# Project_Espro.net
KiCad netlist of a schematic drawn in EasyEDA
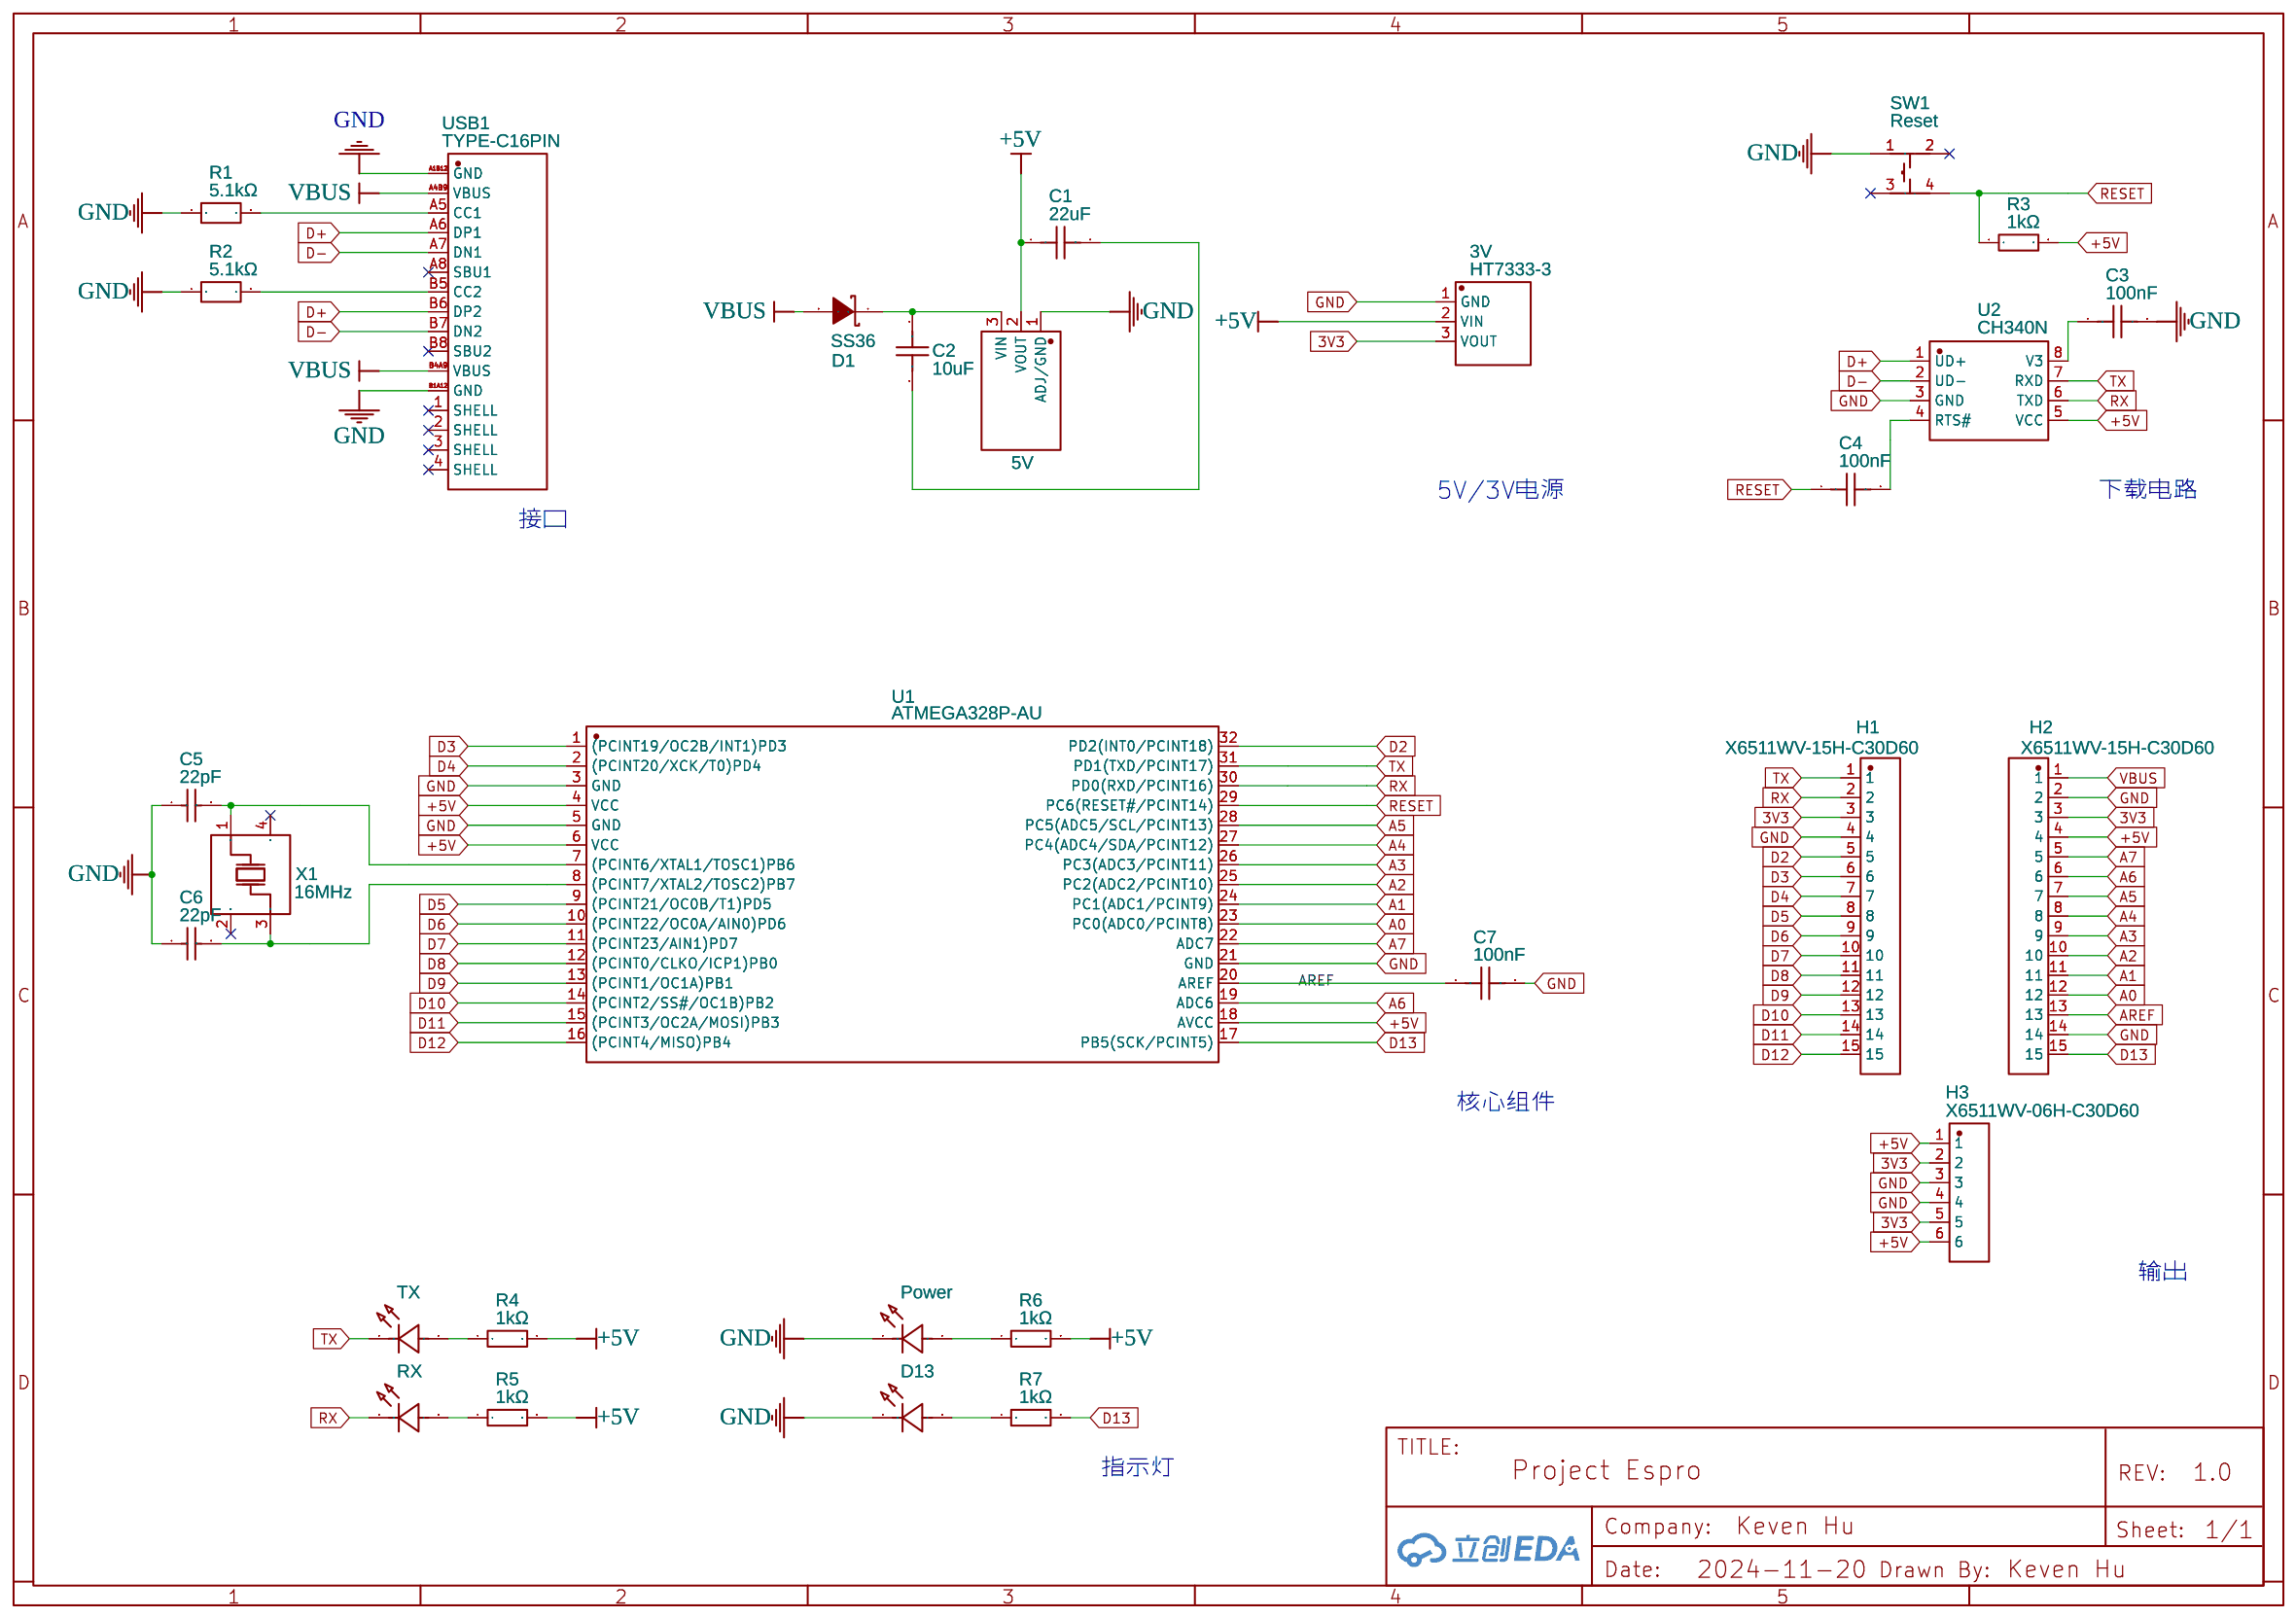
[diagram p0: schematic sheet]

(export (version "E")
  (design (tool "Eeschema 10.0.6"))
  (components
    (comp (ref "3V")
      (value "HT7333-3")
      (fields (field (name "Manufacturer") "HOLTEK"))
      (libsource (lib "") (part "HT7333-3"))
    )
    (comp (ref "5V")
      (value "5V")
      (fields (field (name "Manufacturer Part") "AMS1117-5.0") (field (name "Manufacturer") "Slkor(萨科微)"))
      (libsource (lib "") (part "AMS1117-5.0_C880753"))
    )
    (comp (ref "C1")
      (value "22uF")
      (fields
        (field (name "Manufacturer Part") "HGC0603R5226M100NTHJ")
        (field (name "Manufacturer") "Chinocera(华瓷)")
      )
      (libsource (lib "") (part "HGC0603R5226M100NTHJ"))
    )
    (comp (ref "C2")
      (value "10uF")
      (fields
        (field (name "Manufacturer Part") "CGA0603X5R106K100JT")
        (field (name "Manufacturer") "HRE(芯声)")
      )
      (libsource (lib "") (part "CGA0603X5R106K100JT"))
    )
    (comp (ref "C3")
      (value "100nF")
      (fields
        (field (name "Manufacturer Part") "CGA0603X7R104K500JT")
        (field (name "Manufacturer") "HRE(芯声)")
      )
      (libsource (lib "") (part "CGA0603X7R104K500JT"))
    )
    (comp (ref "C4")
      (value "100nF")
      (fields
        (field (name "Manufacturer Part") "CGA0603X7R104K500JT")
        (field (name "Manufacturer") "HRE(芯声)")
      )
      (libsource (lib "") (part "CGA0603X7R104K500JT"))
    )
    (comp (ref "C5")
      (value "22pF")
      (fields
        (field (name "Manufacturer Part") "CC0603JRNPO9BN220")
        (field (name "Manufacturer") "YAGEO(国巨)")
      )
      (libsource (lib "") (part "CC0603JRNPO9BN220"))
    )
    (comp (ref "C6")
      (value "22pF")
      (fields
        (field (name "Manufacturer Part") "CC0603JRNPO9BN220")
        (field (name "Manufacturer") "YAGEO(国巨)")
      )
      (libsource (lib "") (part "CC0603JRNPO9BN220"))
    )
    (comp (ref "C7")
      (value "100nF")
      (fields
        (field (name "Manufacturer Part") "CGA0603X7R104K500JT")
        (field (name "Manufacturer") "HRE(芯声)")
      )
      (libsource (lib "") (part "CGA0603X7R104K500JT"))
    )
    (comp (ref "D1")
      (value "SS36")
      (fields (field (name "Manufacturer") "MDD"))
      (libsource (lib "") (part "SS36"))
    )
    (comp (ref "H1")
      (value "X6511WV-15H-C30D60")
      (fields (field (name "Manufacturer") "XKB Connectivity"))
      (libsource (lib "") (part "X6511WV-15H-C30D60"))
    )
    (comp (ref "H2")
      (value "X6511WV-15H-C30D60")
      (fields (field (name "Manufacturer") "XKB Connectivity"))
      (libsource (lib "") (part "X6511WV-15H-C30D60_1"))
    )
    (comp (ref "H3")
      (value "X6511WV-06H-C30D60")
      (fields (field (name "Manufacturer") "XKB Connectivity"))
      (libsource (lib "") (part "X6511WV-06H-C30D60"))
    )
    (comp (ref "LED1")
      (value "TX")
      (fields
        (field (name "Manufacturer Part") "XL-1608UWC-06A")
        (field (name "Manufacturer") "XINGLIGHT(成兴光)")
      )
      (libsource (lib "") (part "XL-1608UWC-06A"))
    )
    (comp (ref "LED2")
      (value "RX")
      (fields
        (field (name "Manufacturer Part") "XL-1608UWC-06A")
        (field (name "Manufacturer") "XINGLIGHT(成兴光)")
      )
      (libsource (lib "") (part "XL-1608UWC-06A"))
    )
    (comp (ref "LED3")
      (value "Power")
      (fields
        (field (name "Manufacturer Part") "XL-1608UWC-06A")
        (field (name "Manufacturer") "XINGLIGHT(成兴光)")
      )
      (libsource (lib "") (part "XL-1608UWC-06A"))
    )
    (comp (ref "LED4")
      (value "D13")
      (fields
        (field (name "Manufacturer Part") "XL-1608UWC-06A")
        (field (name "Manufacturer") "XINGLIGHT(成兴光)")
      )
      (libsource (lib "") (part "XL-1608UWC-06A"))
    )
    (comp (ref "R1")
      (value "5.1kΩ")
      (fields (field (name "Manufacturer Part") "FRC0603F5101TS") (field (name "Manufacturer") "FOJAN(富捷)"))
      (libsource (lib "") (part "FRC0603F5101TS"))
    )
    (comp (ref "R2")
      (value "5.1kΩ")
      (fields (field (name "Manufacturer Part") "FRC0603F5101TS") (field (name "Manufacturer") "FOJAN(富捷)"))
      (libsource (lib "") (part "FRC0603F5101TS"))
    )
    (comp (ref "R3")
      (value "1kΩ")
      (fields (field (name "Manufacturer Part") "RC0603FR-071KL") (field (name "Manufacturer") "YAGEO(国巨)"))
      (libsource (lib "") (part "RC0603FR-071KL"))
    )
    (comp (ref "R4")
      (value "1kΩ")
      (fields (field (name "Manufacturer Part") "RC0603FR-071KL") (field (name "Manufacturer") "YAGEO(国巨)"))
      (libsource (lib "") (part "RC0603FR-071KL"))
    )
    (comp (ref "R5")
      (value "1kΩ")
      (fields (field (name "Manufacturer Part") "RC0603FR-071KL") (field (name "Manufacturer") "YAGEO(国巨)"))
      (libsource (lib "") (part "RC0603FR-071KL"))
    )
    (comp (ref "R6")
      (value "1kΩ")
      (fields (field (name "Manufacturer Part") "RC0603FR-071KL") (field (name "Manufacturer") "YAGEO(国巨)"))
      (libsource (lib "") (part "RC0603FR-071KL"))
    )
    (comp (ref "R7")
      (value "1kΩ")
      (fields (field (name "Manufacturer Part") "RC0603FR-071KL") (field (name "Manufacturer") "YAGEO(国巨)"))
      (libsource (lib "") (part "RC0603FR-071KL"))
    )
    (comp (ref "SW1")
      (value "Reset")
      (fields (field (name "Manufacturer Part") "TS3425BA") (field (name "Manufacturer") "SHOU HAN(首韩)"))
      (libsource (lib "") (part "TS3425BA"))
    )
    (comp (ref "U1")
      (value "ATMEGA328P-AU")
      (fields (field (name "Manufacturer") "MICROCHIP"))
      (libsource (lib "") (part "ATMEGA328P-AU"))
    )
    (comp (ref "U2")
      (value "CH340N")
      (fields (field (name "Manufacturer") "WCH(Jiangsu Qin Heng)"))
      (libsource (lib "") (part "CH340N"))
    )
    (comp (ref "USB1")
      (value "TYPE-C16PIN")
      (fields (field (name "Manufacturer") "SHOU HAN"))
      (libsource (lib "") (part "TYPE-C16PIN"))
    )
    (comp (ref "X1")
      (value "16MHz")
      (fields (field (name "Manufacturer Part") "X322516MLB4SI") (field (name "Manufacturer") "YXC"))
      (libsource (lib "") (part "X322516MLB4SI"))
    )
  )
  (nets
    (net (code "1") (name "+5V") (class "Default")
      (node (ref "3V") (pin "2") (pinfunction "VIN_2") (pintype "unspecified"))
      (node (ref "5V") (pin "2") (pinfunction "VOUT_2") (pintype "unspecified"))
      (node (ref "C1") (pin "1") (pinfunction "1_1") (pintype "unspecified"))
      (node (ref "H2") (pin "4") (pinfunction "4_4") (pintype "unspecified"))
      (node (ref "H3") (pin "1") (pinfunction "1_1") (pintype "unspecified"))
      (node (ref "H3") (pin "6") (pinfunction "6_6") (pintype "unspecified"))
      (node (ref "R3") (pin "2") (pinfunction "2_2") (pintype "input"))
      (node (ref "R4") (pin "2") (pinfunction "2_2") (pintype "input"))
      (node (ref "R5") (pin "2") (pinfunction "2_2") (pintype "input"))
      (node (ref "R6") (pin "2") (pinfunction "2_2") (pintype "input"))
      (node (ref "U1") (pin "18") (pinfunction "AVCC_18") (pintype "unspecified"))
      (node (ref "U1") (pin "4") (pinfunction "VCC_4") (pintype "unspecified"))
      (node (ref "U1") (pin "6") (pinfunction "VCC_6") (pintype "unspecified"))
      (node (ref "U2") (pin "5") (pinfunction "VCC_5") (pintype "unspecified"))
    )
    (net (code "2") (name "3V3") (class "Default")
      (node (ref "3V") (pin "3") (pinfunction "VOUT_3") (pintype "unspecified"))
      (node (ref "H1") (pin "3") (pinfunction "3_3") (pintype "unspecified"))
      (node (ref "H2") (pin "3") (pinfunction "3_3") (pintype "unspecified"))
      (node (ref "H3") (pin "2") (pinfunction "2_2") (pintype "unspecified"))
      (node (ref "H3") (pin "5") (pinfunction "5_5") (pintype "unspecified"))
    )
    (net (code "3") (name "A0") (class "Default")
      (node (ref "H2") (pin "12") (pinfunction "12_12") (pintype "unspecified"))
      (node (ref "U1") (pin "23") (pinfunction "PC0(ADC0/PCINT8)_23") (pintype "unspecified"))
    )
    (net (code "4") (name "A1") (class "Default")
      (node (ref "H2") (pin "11") (pinfunction "11_11") (pintype "unspecified"))
      (node (ref "U1") (pin "24") (pinfunction "PC1(ADC1/PCINT9)_24") (pintype "unspecified"))
    )
    (net (code "5") (name "A2") (class "Default")
      (node (ref "H2") (pin "10") (pinfunction "10_10") (pintype "unspecified"))
      (node (ref "U1") (pin "25") (pinfunction "PC2(ADC2/PCINT10)_25") (pintype "unspecified"))
    )
    (net (code "6") (name "A3") (class "Default")
      (node (ref "H2") (pin "9") (pinfunction "9_9") (pintype "unspecified"))
      (node (ref "U1") (pin "26") (pinfunction "PC3(ADC3/PCINT11)_26") (pintype "unspecified"))
    )
    (net (code "7") (name "A4") (class "Default")
      (node (ref "H2") (pin "8") (pinfunction "8_8") (pintype "unspecified"))
      (node (ref "U1") (pin "27") (pinfunction "PC4(ADC4/SDA/PCINT12)_27") (pintype "unspecified"))
    )
    (net (code "8") (name "A5") (class "Default")
      (node (ref "H2") (pin "7") (pinfunction "7_7") (pintype "unspecified"))
      (node (ref "U1") (pin "28") (pinfunction "PC5(ADC5/SCL/PCINT13)_28") (pintype "unspecified"))
    )
    (net (code "9") (name "A6") (class "Default")
      (node (ref "H2") (pin "6") (pinfunction "6_6") (pintype "unspecified"))
      (node (ref "U1") (pin "19") (pinfunction "ADC6_19") (pintype "unspecified"))
    )
    (net (code "10") (name "A7") (class "Default")
      (node (ref "H2") (pin "5") (pinfunction "5_5") (pintype "unspecified"))
      (node (ref "U1") (pin "22") (pinfunction "ADC7_22") (pintype "unspecified"))
    )
    (net (code "11") (name "AREF") (class "Default")
      (node (ref "C7") (pin "1") (pinfunction "1_1") (pintype "unspecified"))
      (node (ref "H2") (pin "13") (pinfunction "13_13") (pintype "unspecified"))
      (node (ref "U1") (pin "20") (pinfunction "AREF_20") (pintype "unspecified"))
    )
    (net (code "12") (name "D+") (class "Default")
      (node (ref "U2") (pin "1") (pinfunction "UD+_1") (pintype "unspecified"))
      (node (ref "USB1") (pin "A6") (pinfunction "DP1_A6") (pintype "unspecified"))
      (node (ref "USB1") (pin "B6") (pinfunction "DP2_B6") (pintype "unspecified"))
    )
    (net (code "13") (name "D-") (class "Default")
      (node (ref "U2") (pin "2") (pinfunction "UD-_2") (pintype "unspecified"))
      (node (ref "USB1") (pin "A7") (pinfunction "DN1_A7") (pintype "unspecified"))
      (node (ref "USB1") (pin "B7") (pinfunction "DN2_B7") (pintype "unspecified"))
    )
    (net (code "14") (name "D2") (class "Default")
      (node (ref "H1") (pin "5") (pinfunction "5_5") (pintype "unspecified"))
      (node (ref "U1") (pin "32") (pinfunction "PD2(INT0/PCINT18)_32") (pintype "unspecified"))
    )
    (net (code "15") (name "D3") (class "Default")
      (node (ref "H1") (pin "6") (pinfunction "6_6") (pintype "unspecified"))
      (node (ref "U1") (pin "1") (pinfunction "(PCINT19/OC2B/INT1)PD3_1") (pintype "unspecified"))
    )
    (net (code "16") (name "D4") (class "Default")
      (node (ref "H1") (pin "7") (pinfunction "7_7") (pintype "unspecified"))
      (node (ref "U1") (pin "2") (pinfunction "(PCINT20/XCK/T0)PD4_2") (pintype "unspecified"))
    )
    (net (code "17") (name "D5") (class "Default")
      (node (ref "H1") (pin "8") (pinfunction "8_8") (pintype "unspecified"))
      (node (ref "U1") (pin "9") (pinfunction "(PCINT21/OC0B/T1)PD5_9") (pintype "unspecified"))
    )
    (net (code "18") (name "D6") (class "Default")
      (node (ref "H1") (pin "9") (pinfunction "9_9") (pintype "unspecified"))
      (node (ref "U1") (pin "10") (pinfunction "(PCINT22/OC0A/AIN0)PD6_10") (pintype "unspecified"))
    )
    (net (code "19") (name "D7") (class "Default")
      (node (ref "H1") (pin "10") (pinfunction "10_10") (pintype "unspecified"))
      (node (ref "U1") (pin "11") (pinfunction "(PCINT23/AIN1)PD7_11") (pintype "unspecified"))
    )
    (net (code "20") (name "D8") (class "Default")
      (node (ref "H1") (pin "11") (pinfunction "11_11") (pintype "unspecified"))
      (node (ref "U1") (pin "12") (pinfunction "(PCINT0/CLKO/ICP1)PB0_12") (pintype "unspecified"))
    )
    (net (code "21") (name "D9") (class "Default")
      (node (ref "H1") (pin "12") (pinfunction "12_12") (pintype "unspecified"))
      (node (ref "U1") (pin "13") (pinfunction "(PCINT1/OC1A)PB1_13") (pintype "unspecified"))
    )
    (net (code "22") (name "D10") (class "Default")
      (node (ref "H1") (pin "13") (pinfunction "13_13") (pintype "unspecified"))
      (node (ref "U1") (pin "14") (pinfunction "(PCINT2/SS#/OC1B)PB2_14") (pintype "unspecified"))
    )
    (net (code "23") (name "D11") (class "Default")
      (node (ref "H1") (pin "14") (pinfunction "14_14") (pintype "unspecified"))
      (node (ref "U1") (pin "15") (pinfunction "(PCINT3/OC2A/MOSI)PB3_15") (pintype "unspecified"))
    )
    (net (code "24") (name "D12") (class "Default")
      (node (ref "H1") (pin "15") (pinfunction "15_15") (pintype "unspecified"))
      (node (ref "U1") (pin "16") (pinfunction "(PCINT4/MISO)PB4_16") (pintype "unspecified"))
    )
    (net (code "25") (name "D13") (class "Default")
      (node (ref "H2") (pin "15") (pinfunction "15_15") (pintype "unspecified"))
      (node (ref "R7") (pin "2") (pinfunction "2_2") (pintype "input"))
      (node (ref "U1") (pin "17") (pinfunction "PB5(SCK/PCINT5)_17") (pintype "unspecified"))
    )
    (net (code "26") (name "GND") (class "Default")
      (node (ref "3V") (pin "1") (pinfunction "GND_1") (pintype "unspecified"))
      (node (ref "5V") (pin "1") (pinfunction "ADJ/GND_1") (pintype "unspecified"))
      (node (ref "C3") (pin "2") (pinfunction "2_2") (pintype "unspecified"))
      (node (ref "C5") (pin "1") (pinfunction "1_1") (pintype "input"))
      (node (ref "C6") (pin "1") (pinfunction "1_1") (pintype "input"))
      (node (ref "C7") (pin "2") (pinfunction "2_2") (pintype "unspecified"))
      (node (ref "H1") (pin "4") (pinfunction "4_4") (pintype "unspecified"))
      (node (ref "H2") (pin "14") (pinfunction "14_14") (pintype "unspecified"))
      (node (ref "H2") (pin "2") (pinfunction "2_2") (pintype "unspecified"))
      (node (ref "H3") (pin "3") (pinfunction "3_3") (pintype "unspecified"))
      (node (ref "H3") (pin "4") (pinfunction "4_4") (pintype "unspecified"))
      (node (ref "LED3") (pin "1") (pinfunction "K_1") (pintype "unspecified"))
      (node (ref "LED4") (pin "1") (pinfunction "K_1") (pintype "unspecified"))
      (node (ref "R1") (pin "1") (pinfunction "1_1") (pintype "unspecified"))
      (node (ref "R2") (pin "1") (pinfunction "1_1") (pintype "unspecified"))
      (node (ref "SW1") (pin "1") (pinfunction "1_1") (pintype "unspecified"))
      (node (ref "U1") (pin "21") (pinfunction "GND_21") (pintype "unspecified"))
      (node (ref "U1") (pin "3") (pinfunction "GND_3") (pintype "unspecified"))
      (node (ref "U1") (pin "5") (pinfunction "GND_5") (pintype "unspecified"))
      (node (ref "U2") (pin "3") (pinfunction "GND_3") (pintype "unspecified"))
      (node (ref "USB1") (pin "A1B12") (pinfunction "GND_A1B12") (pintype "unspecified"))
      (node (ref "USB1") (pin "B1A12") (pinfunction "GND_B1A12") (pintype "unspecified"))
    )
    (net (code "27") (name "Net-(5V-VIN)") (class "Default")
      (node (ref "5V") (pin "3") (pinfunction "VIN_3") (pintype "unspecified"))
      (node (ref "C2") (pin "1") (pinfunction "1_1") (pintype "unspecified"))
      (node (ref "D1") (pin "1") (pinfunction "K_1") (pintype "unspecified"))
    )
    (net (code "28") (name "Net-(C1-Pad2)") (class "Default")
      (node (ref "C1") (pin "2") (pinfunction "2_2") (pintype "unspecified"))
      (node (ref "C2") (pin "2") (pinfunction "2_2") (pintype "unspecified"))
    )
    (net (code "29") (name "Net-(LED1-A)") (class "Default")
      (node (ref "LED1") (pin "2") (pinfunction "A_2") (pintype "unspecified"))
      (node (ref "R4") (pin "1") (pinfunction "1_1") (pintype "input"))
    )
    (net (code "30") (name "Net-(LED2-A)") (class "Default")
      (node (ref "LED2") (pin "2") (pinfunction "A_2") (pintype "unspecified"))
      (node (ref "R5") (pin "1") (pinfunction "1_1") (pintype "input"))
    )
    (net (code "31") (name "Net-(LED3-A)") (class "Default")
      (node (ref "LED3") (pin "2") (pinfunction "A_2") (pintype "unspecified"))
      (node (ref "R6") (pin "1") (pinfunction "1_1") (pintype "input"))
    )
    (net (code "32") (name "Net-(LED4-A)") (class "Default")
      (node (ref "LED4") (pin "2") (pinfunction "A_2") (pintype "unspecified"))
      (node (ref "R7") (pin "1") (pinfunction "1_1") (pintype "input"))
    )
    (net (code "33") (name "Net-(U1-(PCINT6{slash}XTAL1{slash}TOSC1)PB6)") (class "Default")
      (node (ref "C5") (pin "2") (pinfunction "2_2") (pintype "input"))
      (node (ref "U1") (pin "7") (pinfunction "(PCINT6/XTAL1/TOSC1)PB6_7") (pintype "unspecified"))
      (node (ref "X1") (pin "1") (pinfunction "OSC1_1") (pintype "unspecified"))
    )
    (net (code "34") (name "Net-(U1-(PCINT7{slash}XTAL2{slash}TOSC2)PB7)") (class "Default")
      (node (ref "C6") (pin "2") (pinfunction "2_2") (pintype "input"))
      (node (ref "U1") (pin "8") (pinfunction "(PCINT7/XTAL2/TOSC2)PB7_8") (pintype "unspecified"))
      (node (ref "X1") (pin "3") (pinfunction "OSC2_3") (pintype "unspecified"))
    )
    (net (code "35") (name "Net-(U2-RTS#)") (class "Default")
      (node (ref "C4") (pin "2") (pinfunction "2_2") (pintype "unspecified"))
      (node (ref "U2") (pin "4") (pinfunction "RTS#_4") (pintype "unspecified"))
    )
    (net (code "36") (name "Net-(U2-V3)") (class "Default")
      (node (ref "C3") (pin "1") (pinfunction "1_1") (pintype "unspecified"))
      (node (ref "U2") (pin "8") (pinfunction "V3_8") (pintype "unspecified"))
    )
    (net (code "37") (name "Net-(USB1-CC1)") (class "Default")
      (node (ref "R1") (pin "2") (pinfunction "2_2") (pintype "unspecified"))
      (node (ref "USB1") (pin "A5") (pinfunction "CC1_A5") (pintype "unspecified"))
    )
    (net (code "38") (name "Net-(USB1-CC2)") (class "Default")
      (node (ref "R2") (pin "2") (pinfunction "2_2") (pintype "unspecified"))
      (node (ref "USB1") (pin "B5") (pinfunction "CC2_B5") (pintype "unspecified"))
    )
    (net (code "39") (name "RESET") (class "Default")
      (node (ref "C4") (pin "1") (pinfunction "1_1") (pintype "unspecified"))
      (node (ref "R3") (pin "1") (pinfunction "1_1") (pintype "input"))
      (node (ref "SW1") (pin "4") (pinfunction "4_4") (pintype "unspecified"))
      (node (ref "U1") (pin "29") (pinfunction "PC6(RESET#/PCINT14)_29") (pintype "unspecified"))
    )
    (net (code "40") (name "RX") (class "Default")
      (node (ref "H1") (pin "2") (pinfunction "2_2") (pintype "unspecified"))
      (node (ref "LED2") (pin "1") (pinfunction "K_1") (pintype "unspecified"))
      (node (ref "U1") (pin "30") (pinfunction "PD0(RXD/PCINT16)_30") (pintype "unspecified"))
      (node (ref "U2") (pin "6") (pinfunction "TXD_6") (pintype "unspecified"))
    )
    (net (code "41") (name "TX") (class "Default")
      (node (ref "H1") (pin "1") (pinfunction "1_1") (pintype "unspecified"))
      (node (ref "LED1") (pin "1") (pinfunction "K_1") (pintype "unspecified"))
      (node (ref "U1") (pin "31") (pinfunction "PD1(TXD/PCINT17)_31") (pintype "unspecified"))
      (node (ref "U2") (pin "7") (pinfunction "RXD_7") (pintype "unspecified"))
    )
    (net (code "42") (name "VBUS") (class "Default")
      (node (ref "D1") (pin "2") (pinfunction "A_2") (pintype "unspecified"))
      (node (ref "H2") (pin "1") (pinfunction "1_1") (pintype "unspecified"))
      (node (ref "USB1") (pin "A4B9") (pinfunction "VBUS_A4B9") (pintype "unspecified"))
      (node (ref "USB1") (pin "B4A9") (pinfunction "VBUS_B4A9") (pintype "unspecified"))
    )
    (net (code "43") (name "unconnected-(SW1-Pad2)") (class "Default")
      (node (ref "SW1") (pin "2") (pinfunction "2_2") (pintype "unspecified+no_connect"))
    )
    (net (code "44") (name "unconnected-(SW1-Pad3)") (class "Default")
      (node (ref "SW1") (pin "3") (pinfunction "3_3") (pintype "unspecified+no_connect"))
    )
    (net (code "45") (name "unconnected-(USB1-SBU1-PadA8)") (class "Default")
      (node (ref "USB1") (pin "A8") (pinfunction "SBU1_A8") (pintype "unspecified+no_connect"))
    )
    (net (code "46") (name "unconnected-(USB1-SBU2-PadB8)") (class "Default")
      (node (ref "USB1") (pin "B8") (pinfunction "SBU2_B8") (pintype "unspecified+no_connect"))
    )
    (net (code "47") (name "unconnected-(USB1-SHELL-Pad1)") (class "Default")
      (node (ref "USB1") (pin "1") (pinfunction "SHELL_1") (pintype "unspecified+no_connect"))
    )
    (net (code "48") (name "unconnected-(USB1-SHELL-Pad2)") (class "Default")
      (node (ref "USB1") (pin "2") (pinfunction "SHELL_2") (pintype "unspecified+no_connect"))
    )
    (net (code "49") (name "unconnected-(USB1-SHELL-Pad3)") (class "Default")
      (node (ref "USB1") (pin "3") (pinfunction "SHELL_3") (pintype "unspecified+no_connect"))
    )
    (net (code "50") (name "unconnected-(USB1-SHELL-Pad4)") (class "Default")
      (node (ref "USB1") (pin "4") (pinfunction "SHELL_4") (pintype "unspecified+no_connect"))
    )
    (net (code "51") (name "unconnected-(X1-GND-Pad2)") (class "Default")
      (node (ref "X1") (pin "2") (pinfunction "GND_2") (pintype "unspecified+no_connect"))
    )
    (net (code "52") (name "unconnected-(X1-GND-Pad4)") (class "Default")
      (node (ref "X1") (pin "4") (pinfunction "GND_4") (pintype "unspecified+no_connect"))
    )
  )
)
